# miditendo_rev3.net
KiCad netlist of a schematic drawn in EAGLE
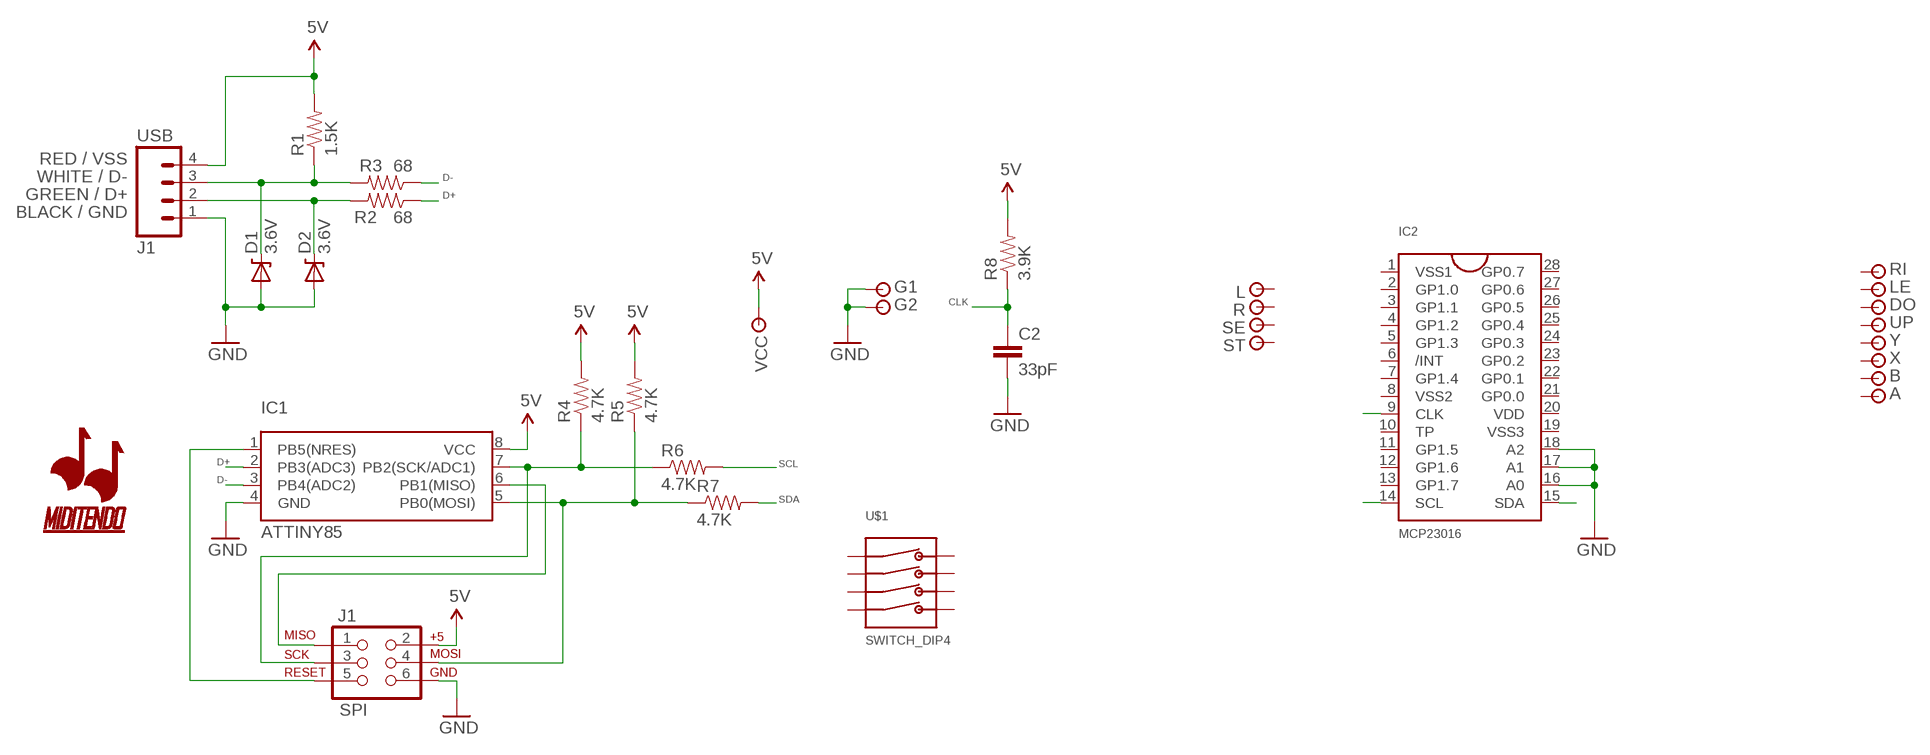
[diagram p0: schematic, sheet 1]

(export (version "E")
  (design (tool "Eeschema 10.0.6"))
  (components
    (comp (ref "A")
      (value "WIRE_JOINT")
      (footprint "eagle-import:THSOLDERPOINT")
      (libsource (lib "eagle-import") (part "WIRE_JOINT"))
    )
    (comp (ref "B")
      (value "WIRE_JOINT")
      (footprint "eagle-import:THSOLDERPOINT")
      (libsource (lib "eagle-import") (part "WIRE_JOINT"))
    )
    (comp (ref "C2")
      (value "33pF")
      (footprint "eagle-import:0805")
      (libsource (lib "eagle-import") (part "CAPACITOR0805"))
    )
    (comp (ref "D1")
      (value "3.6V")
      (footprint "eagle-import:DIODE-ZENER")
      (libsource (lib "eagle-import") (part "DIODE-ZENERPTH"))
    )
    (comp (ref "D2")
      (value "3.6V")
      (footprint "eagle-import:DIODE-ZENER")
      (libsource (lib "eagle-import") (part "DIODE-ZENERPTH"))
    )
    (comp (ref "DO")
      (value "WIRE_JOINT")
      (footprint "eagle-import:THSOLDERPOINT")
      (libsource (lib "eagle-import") (part "WIRE_JOINT"))
    )
    (comp (ref "G1")
      (value "WIRE_JOINT")
      (footprint "eagle-import:THSOLDERPOINT")
      (libsource (lib "eagle-import") (part "WIRE_JOINT"))
    )
    (comp (ref "G2")
      (value "WIRE_JOINT")
      (footprint "eagle-import:THSOLDERPOINT")
      (libsource (lib "eagle-import") (part "WIRE_JOINT"))
    )
    (comp (ref "IC1")
      (value "ATTINY85")
      (footprint "eagle-import:SOIC8-EIAJ")
      (libsource (lib "eagle-import") (part "ATTINY85SOIC"))
    )
    (comp (ref "IC2")
      (value "MCP23016")
      (footprint "eagle-import:SOIC28")
      (libsource (lib "eagle-import") (part "MCP23016SOIC28"))
    )
    (comp (ref "J1")
      (value "SPI")
      (footprint "eagle-import:2X3-NS")
      (libsource (lib "eagle-import") (part "AVR_SPI_PRG_6NS"))
    )
    (comp (ref "L")
      (value "WIRE_JOINT")
      (footprint "eagle-import:THSOLDERPOINT")
      (libsource (lib "eagle-import") (part "WIRE_JOINT"))
    )
    (comp (ref "LE")
      (value "WIRE_JOINT")
      (footprint "eagle-import:THSOLDERPOINT")
      (libsource (lib "eagle-import") (part "WIRE_JOINT"))
    )
    (comp (ref "R")
      (value "WIRE_JOINT")
      (footprint "eagle-import:THSOLDERPOINT")
      (libsource (lib "eagle-import") (part "WIRE_JOINT"))
    )
    (comp (ref "R1")
      (value "1.5K")
      (footprint "eagle-import:0805")
      (libsource (lib "eagle-import") (part "RESISTOR0805"))
    )
    (comp (ref "R2")
      (value "68")
      (footprint "eagle-import:0805")
      (libsource (lib "eagle-import") (part "RESISTOR0805"))
    )
    (comp (ref "R3")
      (value "68")
      (footprint "eagle-import:0805")
      (libsource (lib "eagle-import") (part "RESISTOR0805"))
    )
    (comp (ref "R4")
      (value "4.7K")
      (footprint "eagle-import:0805")
      (libsource (lib "eagle-import") (part "RESISTOR0805"))
    )
    (comp (ref "R5")
      (value "4.7K")
      (footprint "eagle-import:0805")
      (libsource (lib "eagle-import") (part "RESISTOR0805"))
    )
    (comp (ref "R6")
      (value "4.7K")
      (footprint "eagle-import:0805")
      (libsource (lib "eagle-import") (part "RESISTOR0805"))
    )
    (comp (ref "R7")
      (value "4.7K")
      (footprint "eagle-import:0805")
      (libsource (lib "eagle-import") (part "RESISTOR0805"))
    )
    (comp (ref "R8")
      (value "3.9K")
      (footprint "eagle-import:0805")
      (libsource (lib "eagle-import") (part "RESISTOR0805"))
    )
    (comp (ref "RI")
      (value "WIRE_JOINT")
      (footprint "eagle-import:THSOLDERPOINT")
      (libsource (lib "eagle-import") (part "WIRE_JOINT"))
    )
    (comp (ref "SE")
      (value "WIRE_JOINT")
      (footprint "eagle-import:THSOLDERPOINT")
      (libsource (lib "eagle-import") (part "WIRE_JOINT"))
    )
    (comp (ref "ST")
      (value "WIRE_JOINT")
      (footprint "eagle-import:THSOLDERPOINT")
      (libsource (lib "eagle-import") (part "WIRE_JOINT"))
    )
    (comp (ref "U$1")
      (value "SWITCH_DIP4")
      (footprint "eagle-import:SWITCH_4DIP")
      (libsource (lib "eagle-import") (part "SWITCH_DIP4"))
    )
    (comp (ref "U$2")
      (value "MIDITENDO")
      (footprint "eagle-import:MIDITENDO")
      (libsource (lib "eagle-import") (part "MIDITENDO"))
    )
    (comp (ref "UP")
      (value "WIRE_JOINT")
      (footprint "eagle-import:THSOLDERPOINT")
      (libsource (lib "eagle-import") (part "WIRE_JOINT"))
    )
    (comp (ref "USB")
      (value "J1")
      (footprint "eagle-import:1X04_LONGPADS")
      (libsource (lib "eagle-import") (part "M04LONGPADS"))
    )
    (comp (ref "VCC")
      (value "WIRE_JOINT")
      (footprint "eagle-import:THSOLDERPOINT")
      (libsource (lib "eagle-import") (part "WIRE_JOINT"))
    )
    (comp (ref "X")
      (value "WIRE_JOINT")
      (footprint "eagle-import:THSOLDERPOINT")
      (libsource (lib "eagle-import") (part "WIRE_JOINT"))
    )
    (comp (ref "Y")
      (value "WIRE_JOINT")
      (footprint "eagle-import:THSOLDERPOINT")
      (libsource (lib "eagle-import") (part "WIRE_JOINT"))
    )
  )
  (nets
    (net (code "1") (name "/CLK") (class "Default")
      (node (ref "C2") (pin "1") (pinfunction "1_1") (pintype "passive"))
      (node (ref "IC2") (pin "9") (pinfunction "CLK_9") (pintype "input"))
      (node (ref "R8") (pin "1") (pinfunction "1_1") (pintype "passive"))
    )
    (net (code "2") (name "/D+") (class "Default")
      (node (ref "IC1") (pin "2") (pinfunction "PB3(ADC3)_2") (pintype "bidirectional"))
      (node (ref "R2") (pin "1") (pinfunction "1_1") (pintype "passive"))
    )
    (net (code "3") (name "/D-") (class "Default")
      (node (ref "IC1") (pin "3") (pinfunction "PB4(ADC2)_3") (pintype "bidirectional"))
      (node (ref "R3") (pin "1") (pinfunction "1_1") (pintype "passive"))
    )
    (net (code "4") (name "/SCL") (class "Default")
      (node (ref "IC2") (pin "14") (pinfunction "SCL_14") (pintype "input"))
      (node (ref "R6") (pin "2") (pinfunction "2_2") (pintype "passive"))
    )
    (net (code "5") (name "/SDA") (class "Default")
      (node (ref "IC2") (pin "15") (pinfunction "SDA_15") (pintype "bidirectional"))
      (node (ref "R7") (pin "2") (pinfunction "2_2") (pintype "passive"))
    )
    (net (code "6") (name "/VDD") (class "Default")
      (node (ref "IC2") (pin "20") (pinfunction "VDD_20") (pintype "power_in"))
    )
    (net (code "7") (name "/VSS1") (class "Default")
      (node (ref "IC2") (pin "1") (pinfunction "VSS1_1") (pintype "power_in"))
    )
    (net (code "8") (name "/VSS2") (class "Default")
      (node (ref "IC2") (pin "8") (pinfunction "VSS2_8") (pintype "power_in"))
    )
    (net (code "9") (name "/VSS3") (class "Default")
      (node (ref "IC2") (pin "19") (pinfunction "VSS3_19") (pintype "power_in"))
    )
    (net (code "10") (name "5V") (class "Default")
      (node (ref "IC1") (pin "8") (pinfunction "VCC_8") (pintype "bidirectional"))
      (node (ref "J1") (pin "2") (pinfunction "2_2") (pintype "passive"))
      (node (ref "R1") (pin "2") (pinfunction "2_2") (pintype "passive"))
      (node (ref "R4") (pin "2") (pinfunction "2_2") (pintype "passive"))
      (node (ref "R5") (pin "2") (pinfunction "2_2") (pintype "passive"))
      (node (ref "R8") (pin "2") (pinfunction "2_2") (pintype "passive"))
      (node (ref "USB") (pin "4") (pinfunction "4_4") (pintype "passive"))
      (node (ref "VCC") (pin "P$1") (pinfunction "P$1_P$1") (pintype "passive"))
    )
    (net (code "11") (name "GND") (class "Default")
      (node (ref "C2") (pin "2") (pinfunction "2_2") (pintype "passive"))
      (node (ref "D1") (pin "P$2") (pinfunction "A_P$2") (pintype "passive"))
      (node (ref "D2") (pin "P$2") (pinfunction "A_P$2") (pintype "passive"))
      (node (ref "G1") (pin "P$1") (pinfunction "P$1_P$1") (pintype "passive"))
      (node (ref "G2") (pin "P$1") (pinfunction "P$1_P$1") (pintype "passive"))
      (node (ref "IC1") (pin "4") (pinfunction "GND_4") (pintype "bidirectional"))
      (node (ref "IC2") (pin "16") (pinfunction "A0_16") (pintype "input"))
      (node (ref "IC2") (pin "17") (pinfunction "A1_17") (pintype "input"))
      (node (ref "IC2") (pin "18") (pinfunction "A2_18") (pintype "input"))
      (node (ref "J1") (pin "6") (pinfunction "6_6") (pintype "passive"))
      (node (ref "USB") (pin "1") (pinfunction "1_1") (pintype "passive"))
    )
    (net (code "12") (name "Net-(D1-C)") (class "Default")
      (node (ref "D1") (pin "P$1") (pinfunction "C_P$1") (pintype "passive"))
      (node (ref "R1") (pin "1") (pinfunction "1_1") (pintype "passive"))
      (node (ref "R3") (pin "2") (pinfunction "2_2") (pintype "passive"))
      (node (ref "USB") (pin "3") (pinfunction "3_3") (pintype "passive"))
    )
    (net (code "13") (name "Net-(D2-C)") (class "Default")
      (node (ref "D2") (pin "P$1") (pinfunction "C_P$1") (pintype "passive"))
      (node (ref "R2") (pin "2") (pinfunction "2_2") (pintype "passive"))
      (node (ref "USB") (pin "2") (pinfunction "2_2") (pintype "passive"))
    )
    (net (code "14") (name "Net-(IC1-PB0(MOSI))") (class "Default")
      (node (ref "IC1") (pin "5") (pinfunction "PB0(MOSI)_5") (pintype "bidirectional"))
      (node (ref "J1") (pin "4") (pinfunction "4_4") (pintype "passive"))
      (node (ref "R5") (pin "1") (pinfunction "1_1") (pintype "passive"))
      (node (ref "R7") (pin "1") (pinfunction "1_1") (pintype "passive"))
    )
    (net (code "15") (name "Net-(IC1-PB1(MISO))") (class "Default")
      (node (ref "IC1") (pin "6") (pinfunction "PB1(MISO)_6") (pintype "bidirectional"))
      (node (ref "J1") (pin "1") (pinfunction "1_1") (pintype "passive"))
    )
    (net (code "16") (name "Net-(IC1-PB2(SCK{slash}ADC1))") (class "Default")
      (node (ref "IC1") (pin "7") (pinfunction "PB2(SCK/ADC1)_7") (pintype "bidirectional"))
      (node (ref "J1") (pin "3") (pinfunction "3_3") (pintype "passive"))
      (node (ref "R4") (pin "1") (pinfunction "1_1") (pintype "passive"))
      (node (ref "R6") (pin "1") (pinfunction "1_1") (pintype "passive"))
    )
    (net (code "17") (name "Net-(IC1-PB5(NRES))") (class "Default")
      (node (ref "IC1") (pin "1") (pinfunction "PB5(NRES)_1") (pintype "bidirectional"))
      (node (ref "J1") (pin "5") (pinfunction "5_5") (pintype "passive"))
    )
    (net (code "18") (name "unconnected-(A-PadP$1)") (class "Default")
      (node (ref "A") (pin "P$1") (pinfunction "P$1_P$1") (pintype "passive"))
    )
    (net (code "19") (name "unconnected-(B-PadP$1)") (class "Default")
      (node (ref "B") (pin "P$1") (pinfunction "P$1_P$1") (pintype "passive"))
    )
    (net (code "20") (name "unconnected-(DO-PadP$1)") (class "Default")
      (node (ref "DO") (pin "P$1") (pinfunction "P$1_P$1") (pintype "passive"))
    )
    (net (code "21") (name "unconnected-(IC2-GP0.0-Pad21)") (class "Default")
      (node (ref "IC2") (pin "21") (pinfunction "GP0.0_21") (pintype "bidirectional"))
    )
    (net (code "22") (name "unconnected-(IC2-GP0.1-Pad22)") (class "Default")
      (node (ref "IC2") (pin "22") (pinfunction "GP0.1_22") (pintype "bidirectional"))
    )
    (net (code "23") (name "unconnected-(IC2-GP0.2-Pad23)") (class "Default")
      (node (ref "IC2") (pin "23") (pinfunction "GP0.2_23") (pintype "bidirectional"))
    )
    (net (code "24") (name "unconnected-(IC2-GP0.3-Pad24)") (class "Default")
      (node (ref "IC2") (pin "24") (pinfunction "GP0.3_24") (pintype "bidirectional"))
    )
    (net (code "25") (name "unconnected-(IC2-GP0.4-Pad25)") (class "Default")
      (node (ref "IC2") (pin "25") (pinfunction "GP0.4_25") (pintype "bidirectional"))
    )
    (net (code "26") (name "unconnected-(IC2-GP0.5-Pad26)") (class "Default")
      (node (ref "IC2") (pin "26") (pinfunction "GP0.5_26") (pintype "bidirectional"))
    )
    (net (code "27") (name "unconnected-(IC2-GP0.6-Pad27)") (class "Default")
      (node (ref "IC2") (pin "27") (pinfunction "GP0.6_27") (pintype "bidirectional"))
    )
    (net (code "28") (name "unconnected-(IC2-GP0.7-Pad28)") (class "Default")
      (node (ref "IC2") (pin "28") (pinfunction "GP0.7_28") (pintype "bidirectional"))
    )
    (net (code "29") (name "unconnected-(IC2-GP1.0-Pad2)") (class "Default")
      (node (ref "IC2") (pin "2") (pinfunction "GP1.0_2") (pintype "bidirectional"))
    )
    (net (code "30") (name "unconnected-(IC2-GP1.1-Pad3)") (class "Default")
      (node (ref "IC2") (pin "3") (pinfunction "GP1.1_3") (pintype "bidirectional"))
    )
    (net (code "31") (name "unconnected-(IC2-GP1.2-Pad4)") (class "Default")
      (node (ref "IC2") (pin "4") (pinfunction "GP1.2_4") (pintype "bidirectional"))
    )
    (net (code "32") (name "unconnected-(IC2-GP1.3-Pad5)") (class "Default")
      (node (ref "IC2") (pin "5") (pinfunction "GP1.3_5") (pintype "bidirectional"))
    )
    (net (code "33") (name "unconnected-(IC2-GP1.4-Pad7)") (class "Default")
      (node (ref "IC2") (pin "7") (pinfunction "GP1.4_7") (pintype "bidirectional"))
    )
    (net (code "34") (name "unconnected-(IC2-GP1.5-Pad11)") (class "Default")
      (node (ref "IC2") (pin "11") (pinfunction "GP1.5_11") (pintype "bidirectional"))
    )
    (net (code "35") (name "unconnected-(IC2-GP1.6-Pad12)") (class "Default")
      (node (ref "IC2") (pin "12") (pinfunction "GP1.6_12") (pintype "bidirectional"))
    )
    (net (code "36") (name "unconnected-(IC2-GP1.7-Pad13)") (class "Default")
      (node (ref "IC2") (pin "13") (pinfunction "GP1.7_13") (pintype "bidirectional"))
    )
    (net (code "37") (name "unconnected-(IC2-TP-Pad10)") (class "Default")
      (node (ref "IC2") (pin "10") (pinfunction "TP_10") (pintype "bidirectional"))
    )
    (net (code "38") (name "unconnected-(IC2-{slash}INT-Pad6)") (class "Default")
      (node (ref "IC2") (pin "6") (pinfunction "/INT_6") (pintype "output"))
    )
    (net (code "39") (name "unconnected-(L-PadP$1)") (class "Default")
      (node (ref "L") (pin "P$1") (pinfunction "P$1_P$1") (pintype "passive"))
    )
    (net (code "40") (name "unconnected-(LE-PadP$1)") (class "Default")
      (node (ref "LE") (pin "P$1") (pinfunction "P$1_P$1") (pintype "passive"))
    )
    (net (code "41") (name "unconnected-(R-PadP$1)") (class "Default")
      (node (ref "R") (pin "P$1") (pinfunction "P$1_P$1") (pintype "passive"))
    )
    (net (code "42") (name "unconnected-(RI-PadP$1)") (class "Default")
      (node (ref "RI") (pin "P$1") (pinfunction "P$1_P$1") (pintype "passive"))
    )
    (net (code "43") (name "unconnected-(SE-PadP$1)") (class "Default")
      (node (ref "SE") (pin "P$1") (pinfunction "P$1_P$1") (pintype "passive"))
    )
    (net (code "44") (name "unconnected-(ST-PadP$1)") (class "Default")
      (node (ref "ST") (pin "P$1") (pinfunction "P$1_P$1") (pintype "passive"))
    )
    (net (code "45") (name "unconnected-(U$1-PadP$1)") (class "Default")
      (node (ref "U$1") (pin "P$1") (pinfunction "P$1_P$1") (pintype "passive"))
    )
    (net (code "46") (name "unconnected-(U$1-PadP$2)") (class "Default")
      (node (ref "U$1") (pin "P$2") (pinfunction "P$2_P$2") (pintype "passive"))
    )
    (net (code "47") (name "unconnected-(U$1-PadP$3)") (class "Default")
      (node (ref "U$1") (pin "P$3") (pinfunction "P$3_P$3") (pintype "passive"))
    )
    (net (code "48") (name "unconnected-(U$1-PadP$4)") (class "Default")
      (node (ref "U$1") (pin "P$4") (pinfunction "P$4_P$4") (pintype "passive"))
    )
    (net (code "49") (name "unconnected-(U$1-PadP$5)") (class "Default")
      (node (ref "U$1") (pin "P$5") (pinfunction "P$5_P$5") (pintype "passive"))
    )
    (net (code "50") (name "unconnected-(U$1-PadP$6)") (class "Default")
      (node (ref "U$1") (pin "P$6") (pinfunction "P$6_P$6") (pintype "passive"))
    )
    (net (code "51") (name "unconnected-(U$1-PadP$7)") (class "Default")
      (node (ref "U$1") (pin "P$7") (pinfunction "P$7_P$7") (pintype "passive"))
    )
    (net (code "52") (name "unconnected-(U$1-PadP$8)") (class "Default")
      (node (ref "U$1") (pin "P$8") (pinfunction "P$8_P$8") (pintype "passive"))
    )
    (net (code "53") (name "unconnected-(UP-PadP$1)") (class "Default")
      (node (ref "UP") (pin "P$1") (pinfunction "P$1_P$1") (pintype "passive"))
    )
    (net (code "54") (name "unconnected-(X-PadP$1)") (class "Default")
      (node (ref "X") (pin "P$1") (pinfunction "P$1_P$1") (pintype "passive"))
    )
    (net (code "55") (name "unconnected-(Y-PadP$1)") (class "Default")
      (node (ref "Y") (pin "P$1") (pinfunction "P$1_P$1") (pintype "passive"))
    )
  )
)
